# W103C.net
KiCad netlist of a schematic drawn in EAGLE
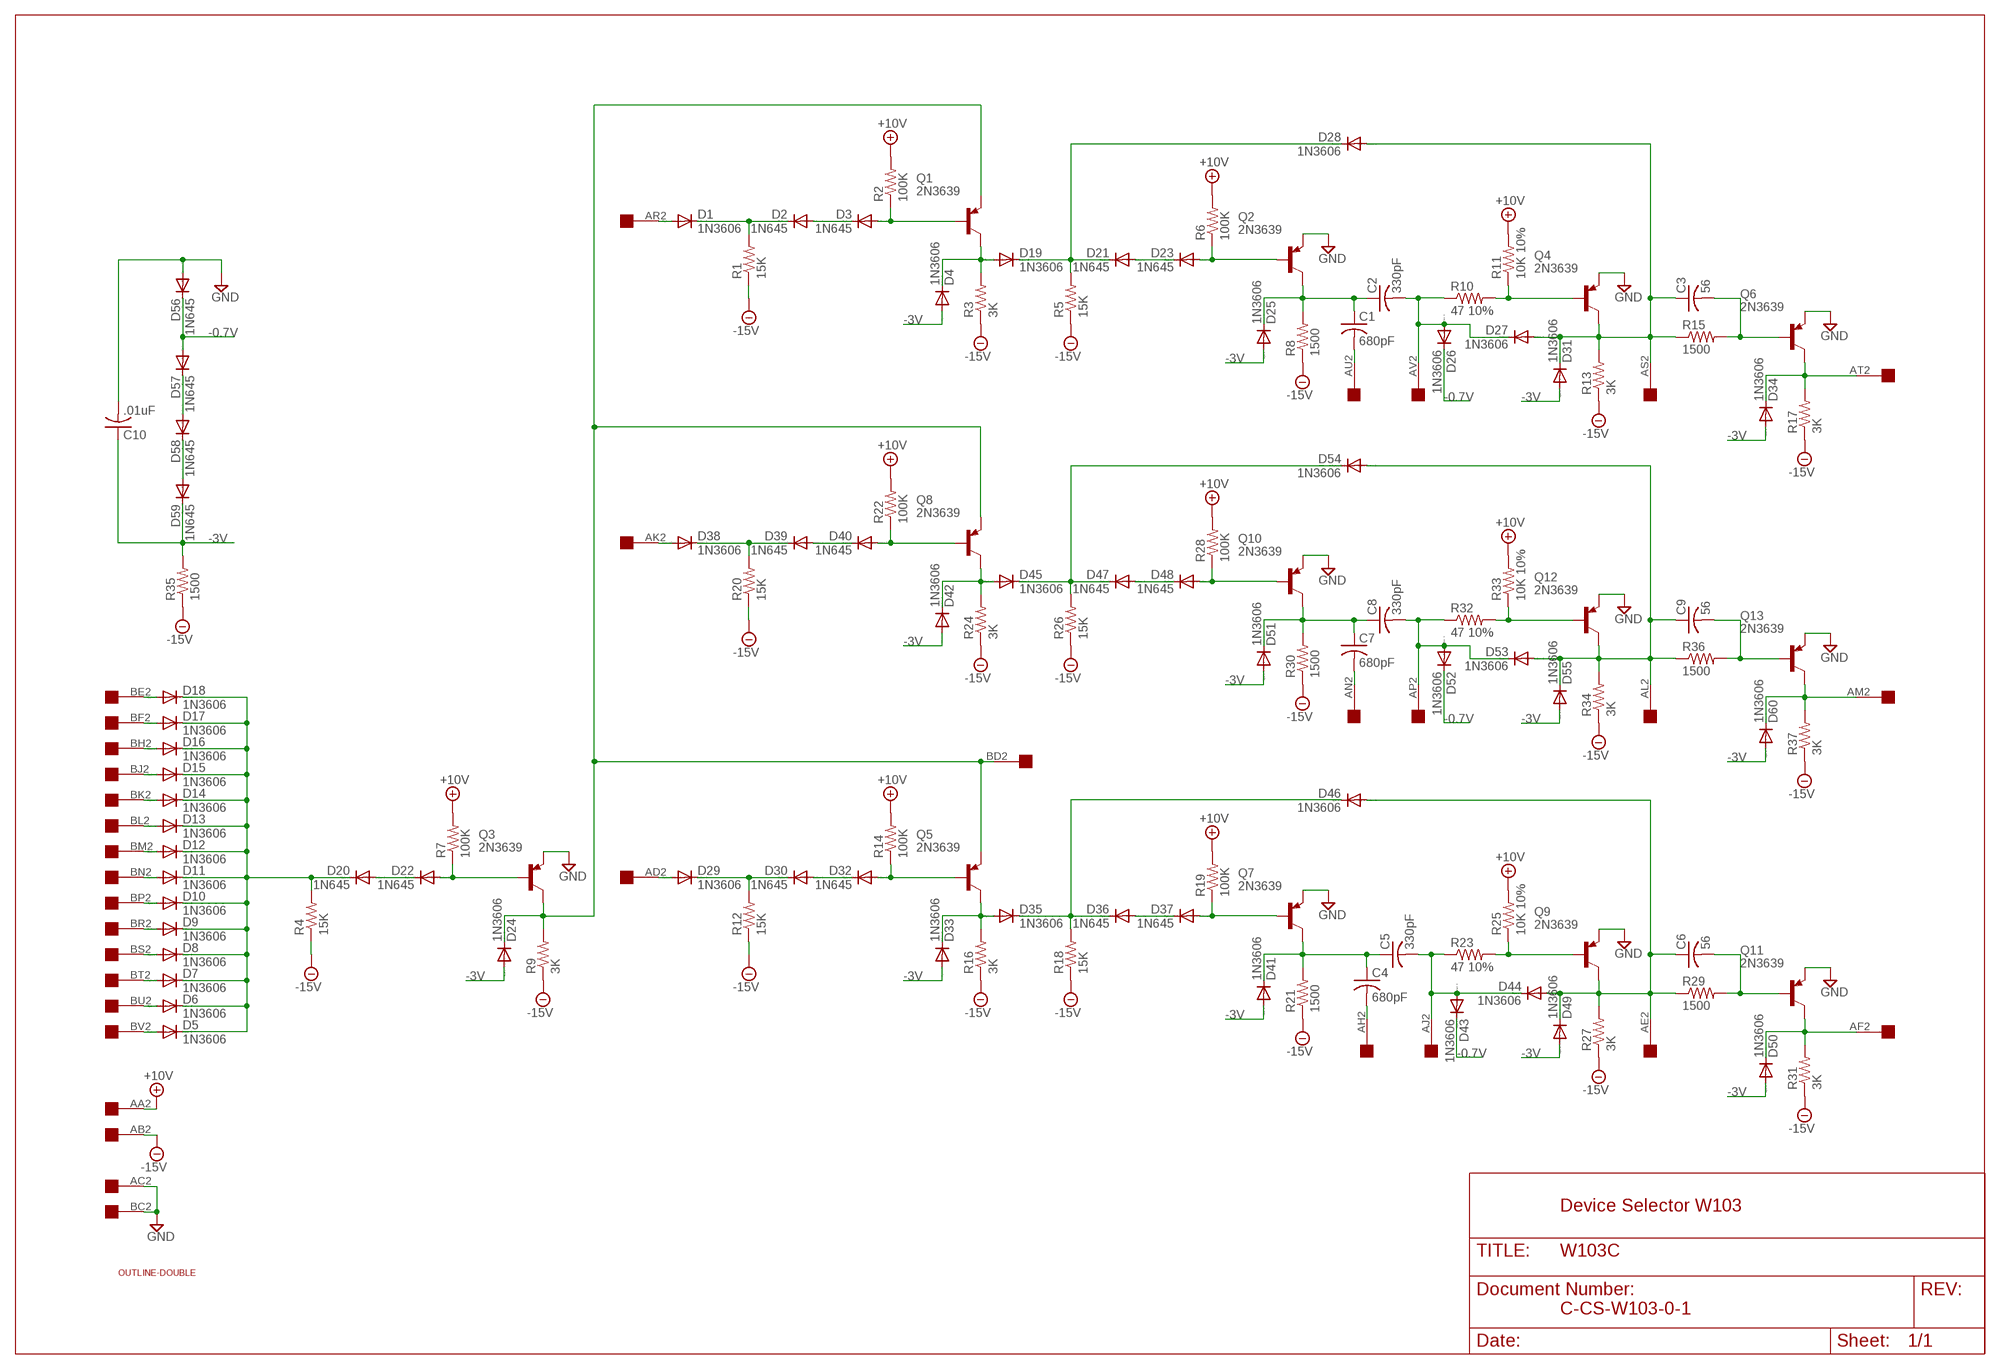
[diagram p0: schematic, sheet 1]

(export (version "E")
  (design (tool "Eeschema 10.0.6"))
  (components
    (comp (ref "C1")
      (value "680pF")
      (footprint "eagle-import:C075-032X103")
      (libsource (lib "eagle-import") (part "C-US075-032X103"))
    )
    (comp (ref "C2")
      (value "330pF")
      (footprint "eagle-import:C075-032X103")
      (libsource (lib "eagle-import") (part "C-US075-032X103"))
    )
    (comp (ref "C3")
      (value "56")
      (footprint "eagle-import:C075-032X103")
      (libsource (lib "eagle-import") (part "C-US075-032X103"))
    )
    (comp (ref "C4")
      (value "680pF")
      (footprint "eagle-import:C075-032X103")
      (libsource (lib "eagle-import") (part "C-US075-032X103"))
    )
    (comp (ref "C5")
      (value "330pF")
      (footprint "eagle-import:C075-032X103")
      (libsource (lib "eagle-import") (part "C-US075-032X103"))
    )
    (comp (ref "C6")
      (value "56")
      (footprint "eagle-import:C075-032X103")
      (libsource (lib "eagle-import") (part "C-US075-032X103"))
    )
    (comp (ref "C7")
      (value "680pF")
      (footprint "eagle-import:C075-032X103")
      (libsource (lib "eagle-import") (part "C-US075-032X103"))
    )
    (comp (ref "C8")
      (value "330pF")
      (footprint "eagle-import:C075-032X103")
      (libsource (lib "eagle-import") (part "C-US075-032X103"))
    )
    (comp (ref "C9")
      (value "56")
      (footprint "eagle-import:C075-032X103")
      (libsource (lib "eagle-import") (part "C-US075-032X103"))
    )
    (comp (ref "C10")
      (value ".01uF")
      (footprint "eagle-import:C075-032X103")
      (libsource (lib "eagle-import") (part "C-US075-032X103"))
    )
    (comp (ref "D1")
      (value "1N3606")
      (footprint "eagle-import:DO35-10")
      (libsource (lib "eagle-import") (part "1N4148DO35-10"))
    )
    (comp (ref "D2")
      (value "1N645")
      (footprint "eagle-import:DO35-10")
      (libsource (lib "eagle-import") (part "1N4148DO35-10"))
    )
    (comp (ref "D3")
      (value "1N645")
      (footprint "eagle-import:DO35-10")
      (libsource (lib "eagle-import") (part "1N4148DO35-10"))
    )
    (comp (ref "D4")
      (value "1N3606")
      (footprint "eagle-import:DO35-10")
      (libsource (lib "eagle-import") (part "1N4148DO35-10"))
    )
    (comp (ref "D5")
      (value "1N3606")
      (footprint "eagle-import:DO35-10")
      (libsource (lib "eagle-import") (part "1N4148DO35-10"))
    )
    (comp (ref "D6")
      (value "1N3606")
      (footprint "eagle-import:DO35-10")
      (libsource (lib "eagle-import") (part "1N4148DO35-10"))
    )
    (comp (ref "D7")
      (value "1N3606")
      (footprint "eagle-import:DO35-10")
      (libsource (lib "eagle-import") (part "1N4148DO35-10"))
    )
    (comp (ref "D8")
      (value "1N3606")
      (footprint "eagle-import:DO35-10")
      (libsource (lib "eagle-import") (part "1N4148DO35-10"))
    )
    (comp (ref "D9")
      (value "1N3606")
      (footprint "eagle-import:DO35-10")
      (libsource (lib "eagle-import") (part "1N4148DO35-10"))
    )
    (comp (ref "D10")
      (value "1N3606")
      (footprint "eagle-import:DO35-10")
      (libsource (lib "eagle-import") (part "1N4148DO35-10"))
    )
    (comp (ref "D11")
      (value "1N3606")
      (footprint "eagle-import:DO35-10")
      (libsource (lib "eagle-import") (part "1N4148DO35-10"))
    )
    (comp (ref "D12")
      (value "1N3606")
      (footprint "eagle-import:DO35-10")
      (libsource (lib "eagle-import") (part "1N4148DO35-10"))
    )
    (comp (ref "D13")
      (value "1N3606")
      (footprint "eagle-import:DO35-10")
      (libsource (lib "eagle-import") (part "1N4148DO35-10"))
    )
    (comp (ref "D14")
      (value "1N3606")
      (footprint "eagle-import:DO35-10")
      (libsource (lib "eagle-import") (part "1N4148DO35-10"))
    )
    (comp (ref "D15")
      (value "1N3606")
      (footprint "eagle-import:DO35-10")
      (libsource (lib "eagle-import") (part "1N4148DO35-10"))
    )
    (comp (ref "D16")
      (value "1N3606")
      (footprint "eagle-import:DO35-10")
      (libsource (lib "eagle-import") (part "1N4148DO35-10"))
    )
    (comp (ref "D17")
      (value "1N3606")
      (footprint "eagle-import:DO35-10")
      (libsource (lib "eagle-import") (part "1N4148DO35-10"))
    )
    (comp (ref "D18")
      (value "1N3606")
      (footprint "eagle-import:DO35-10")
      (libsource (lib "eagle-import") (part "1N4148DO35-10"))
    )
    (comp (ref "D19")
      (value "1N3606")
      (footprint "eagle-import:DO35-10")
      (libsource (lib "eagle-import") (part "1N4148DO35-10"))
    )
    (comp (ref "D20")
      (value "1N645")
      (footprint "eagle-import:DO35-10")
      (libsource (lib "eagle-import") (part "1N4148DO35-10"))
    )
    (comp (ref "D21")
      (value "1N645")
      (footprint "eagle-import:DO35-10")
      (libsource (lib "eagle-import") (part "1N4148DO35-10"))
    )
    (comp (ref "D22")
      (value "1N645")
      (footprint "eagle-import:DO35-10")
      (libsource (lib "eagle-import") (part "1N4148DO35-10"))
    )
    (comp (ref "D23")
      (value "1N645")
      (footprint "eagle-import:DO35-10")
      (libsource (lib "eagle-import") (part "1N4148DO35-10"))
    )
    (comp (ref "D24")
      (value "1N3606")
      (footprint "eagle-import:DO35-10")
      (libsource (lib "eagle-import") (part "1N4148DO35-10"))
    )
    (comp (ref "D25")
      (value "1N3606")
      (footprint "eagle-import:DO35-10")
      (libsource (lib "eagle-import") (part "1N4148DO35-10"))
    )
    (comp (ref "D26")
      (value "1N3606")
      (footprint "eagle-import:DO35-10")
      (libsource (lib "eagle-import") (part "1N4148DO35-10"))
    )
    (comp (ref "D27")
      (value "1N3606")
      (footprint "eagle-import:DO35-10")
      (libsource (lib "eagle-import") (part "1N4148DO35-10"))
    )
    (comp (ref "D28")
      (value "1N3606")
      (footprint "eagle-import:DO35-10")
      (libsource (lib "eagle-import") (part "1N4148DO35-10"))
    )
    (comp (ref "D29")
      (value "1N3606")
      (footprint "eagle-import:DO35-10")
      (libsource (lib "eagle-import") (part "1N4148DO35-10"))
    )
    (comp (ref "D30")
      (value "1N645")
      (footprint "eagle-import:DO35-10")
      (libsource (lib "eagle-import") (part "1N4148DO35-10"))
    )
    (comp (ref "D31")
      (value "1N3606")
      (footprint "eagle-import:DO35-10")
      (libsource (lib "eagle-import") (part "1N4148DO35-10"))
    )
    (comp (ref "D32")
      (value "1N645")
      (footprint "eagle-import:DO35-10")
      (libsource (lib "eagle-import") (part "1N4148DO35-10"))
    )
    (comp (ref "D33")
      (value "1N3606")
      (footprint "eagle-import:DO35-10")
      (libsource (lib "eagle-import") (part "1N4148DO35-10"))
    )
    (comp (ref "D34")
      (value "1N3606")
      (footprint "eagle-import:DO35-10")
      (libsource (lib "eagle-import") (part "1N4148DO35-10"))
    )
    (comp (ref "D35")
      (value "1N3606")
      (footprint "eagle-import:DO35-10")
      (libsource (lib "eagle-import") (part "1N4148DO35-10"))
    )
    (comp (ref "D36")
      (value "1N645")
      (footprint "eagle-import:DO35-10")
      (libsource (lib "eagle-import") (part "1N4148DO35-10"))
    )
    (comp (ref "D37")
      (value "1N645")
      (footprint "eagle-import:DO35-10")
      (libsource (lib "eagle-import") (part "1N4148DO35-10"))
    )
    (comp (ref "D38")
      (value "1N3606")
      (footprint "eagle-import:DO35-10")
      (libsource (lib "eagle-import") (part "1N4148DO35-10"))
    )
    (comp (ref "D39")
      (value "1N645")
      (footprint "eagle-import:DO35-10")
      (libsource (lib "eagle-import") (part "1N4148DO35-10"))
    )
    (comp (ref "D40")
      (value "1N645")
      (footprint "eagle-import:DO35-10")
      (libsource (lib "eagle-import") (part "1N4148DO35-10"))
    )
    (comp (ref "D41")
      (value "1N3606")
      (footprint "eagle-import:DO35-10")
      (libsource (lib "eagle-import") (part "1N4148DO35-10"))
    )
    (comp (ref "D42")
      (value "1N3606")
      (footprint "eagle-import:DO35-10")
      (libsource (lib "eagle-import") (part "1N4148DO35-10"))
    )
    (comp (ref "D43")
      (value "1N3606")
      (footprint "eagle-import:DO35-10")
      (libsource (lib "eagle-import") (part "1N4148DO35-10"))
    )
    (comp (ref "D44")
      (value "1N3606")
      (footprint "eagle-import:DO35-10")
      (libsource (lib "eagle-import") (part "1N4148DO35-10"))
    )
    (comp (ref "D45")
      (value "1N3606")
      (footprint "eagle-import:DO35-10")
      (libsource (lib "eagle-import") (part "1N4148DO35-10"))
    )
    (comp (ref "D46")
      (value "1N3606")
      (footprint "eagle-import:DO35-10")
      (libsource (lib "eagle-import") (part "1N4148DO35-10"))
    )
    (comp (ref "D47")
      (value "1N645")
      (footprint "eagle-import:DO35-10")
      (libsource (lib "eagle-import") (part "1N4148DO35-10"))
    )
    (comp (ref "D48")
      (value "1N645")
      (footprint "eagle-import:DO35-10")
      (libsource (lib "eagle-import") (part "1N4148DO35-10"))
    )
    (comp (ref "D49")
      (value "1N3606")
      (footprint "eagle-import:DO35-10")
      (libsource (lib "eagle-import") (part "1N4148DO35-10"))
    )
    (comp (ref "D50")
      (value "1N3606")
      (footprint "eagle-import:DO35-10")
      (libsource (lib "eagle-import") (part "1N4148DO35-10"))
    )
    (comp (ref "D51")
      (value "1N3606")
      (footprint "eagle-import:DO35-10")
      (libsource (lib "eagle-import") (part "1N4148DO35-10"))
    )
    (comp (ref "D52")
      (value "1N3606")
      (footprint "eagle-import:DO35-10")
      (libsource (lib "eagle-import") (part "1N4148DO35-10"))
    )
    (comp (ref "D53")
      (value "1N3606")
      (footprint "eagle-import:DO35-10")
      (libsource (lib "eagle-import") (part "1N4148DO35-10"))
    )
    (comp (ref "D54")
      (value "1N3606")
      (footprint "eagle-import:DO35-10")
      (libsource (lib "eagle-import") (part "1N4148DO35-10"))
    )
    (comp (ref "D55")
      (value "1N3606")
      (footprint "eagle-import:DO35-10")
      (libsource (lib "eagle-import") (part "1N4148DO35-10"))
    )
    (comp (ref "D56")
      (value "1N645")
      (footprint "eagle-import:DO35-10")
      (libsource (lib "eagle-import") (part "1N4148DO35-10"))
    )
    (comp (ref "D57")
      (value "1N645")
      (footprint "eagle-import:DO35-10")
      (libsource (lib "eagle-import") (part "1N4148DO35-10"))
    )
    (comp (ref "D58")
      (value "1N645")
      (footprint "eagle-import:DO35-10")
      (libsource (lib "eagle-import") (part "1N4148DO35-10"))
    )
    (comp (ref "D59")
      (value "1N645")
      (footprint "eagle-import:DO35-10")
      (libsource (lib "eagle-import") (part "1N4148DO35-10"))
    )
    (comp (ref "D60")
      (value "1N3606")
      (footprint "eagle-import:DO35-10")
      (libsource (lib "eagle-import") (part "1N4148DO35-10"))
    )
    (comp (ref "Q1")
      (value "2N3639")
      (footprint "eagle-import:TO39")
      (libsource (lib "eagle-import") (part "2N2904"))
    )
    (comp (ref "Q2")
      (value "2N3639")
      (footprint "eagle-import:TO39")
      (libsource (lib "eagle-import") (part "2N2904"))
    )
    (comp (ref "Q3")
      (value "2N3639")
      (footprint "eagle-import:TO39")
      (libsource (lib "eagle-import") (part "2N2904"))
    )
    (comp (ref "Q4")
      (value "2N3639")
      (footprint "eagle-import:TO39")
      (libsource (lib "eagle-import") (part "2N2904"))
    )
    (comp (ref "Q5")
      (value "2N3639")
      (footprint "eagle-import:TO39")
      (libsource (lib "eagle-import") (part "2N2904"))
    )
    (comp (ref "Q6")
      (value "2N3639")
      (footprint "eagle-import:TO39")
      (libsource (lib "eagle-import") (part "2N2904"))
    )
    (comp (ref "Q7")
      (value "2N3639")
      (footprint "eagle-import:TO39")
      (libsource (lib "eagle-import") (part "2N2904"))
    )
    (comp (ref "Q8")
      (value "2N3639")
      (footprint "eagle-import:TO39")
      (libsource (lib "eagle-import") (part "2N2904"))
    )
    (comp (ref "Q9")
      (value "2N3639")
      (footprint "eagle-import:TO39")
      (libsource (lib "eagle-import") (part "2N2904"))
    )
    (comp (ref "Q10")
      (value "2N3639")
      (footprint "eagle-import:TO39")
      (libsource (lib "eagle-import") (part "2N2904"))
    )
    (comp (ref "Q11")
      (value "2N3639")
      (footprint "eagle-import:TO39")
      (libsource (lib "eagle-import") (part "2N2904"))
    )
    (comp (ref "Q12")
      (value "2N3639")
      (footprint "eagle-import:TO39")
      (libsource (lib "eagle-import") (part "2N2904"))
    )
    (comp (ref "Q13")
      (value "2N3639")
      (footprint "eagle-import:TO39")
      (libsource (lib "eagle-import") (part "2N2904"))
    )
    (comp (ref "R1")
      (value "15K")
      (footprint "eagle-import:0207_10")
      (libsource (lib "eagle-import") (part "R-US_0207/10"))
    )
    (comp (ref "R2")
      (value "100K")
      (footprint "eagle-import:0207_10")
      (libsource (lib "eagle-import") (part "R-US_0207/10"))
    )
    (comp (ref "R3")
      (value "3K")
      (footprint "eagle-import:0207_10")
      (libsource (lib "eagle-import") (part "R-US_0207/10"))
    )
    (comp (ref "R4")
      (value "15K")
      (footprint "eagle-import:0207_10")
      (libsource (lib "eagle-import") (part "R-US_0207/10"))
    )
    (comp (ref "R5")
      (value "15K")
      (footprint "eagle-import:0207_10")
      (libsource (lib "eagle-import") (part "R-US_0207/10"))
    )
    (comp (ref "R6")
      (value "100K")
      (footprint "eagle-import:0207_10")
      (libsource (lib "eagle-import") (part "R-US_0207/10"))
    )
    (comp (ref "R7")
      (value "100K")
      (footprint "eagle-import:0207_10")
      (libsource (lib "eagle-import") (part "R-US_0207/10"))
    )
    (comp (ref "R8")
      (value "1500")
      (footprint "eagle-import:0207_10")
      (libsource (lib "eagle-import") (part "R-US_0207/10"))
    )
    (comp (ref "R9")
      (value "3K")
      (footprint "eagle-import:0207_10")
      (libsource (lib "eagle-import") (part "R-US_0207/10"))
    )
    (comp (ref "R10")
      (value "47 10%")
      (footprint "eagle-import:0207_10")
      (libsource (lib "eagle-import") (part "R-US_0207/10"))
    )
    (comp (ref "R11")
      (value "10K 10%")
      (footprint "eagle-import:0207_10")
      (libsource (lib "eagle-import") (part "R-US_0207/10"))
    )
    (comp (ref "R12")
      (value "15K")
      (footprint "eagle-import:0207_10")
      (libsource (lib "eagle-import") (part "R-US_0207/10"))
    )
    (comp (ref "R13")
      (value "3K")
      (footprint "eagle-import:0207_10")
      (libsource (lib "eagle-import") (part "R-US_0207/10"))
    )
    (comp (ref "R14")
      (value "100K")
      (footprint "eagle-import:0207_10")
      (libsource (lib "eagle-import") (part "R-US_0207/10"))
    )
    (comp (ref "R15")
      (value "1500")
      (footprint "eagle-import:0207_10")
      (libsource (lib "eagle-import") (part "R-US_0207/10"))
    )
    (comp (ref "R16")
      (value "3K")
      (footprint "eagle-import:0207_10")
      (libsource (lib "eagle-import") (part "R-US_0207/10"))
    )
    (comp (ref "R17")
      (value "3K")
      (footprint "eagle-import:0207_10")
      (libsource (lib "eagle-import") (part "R-US_0207/10"))
    )
    (comp (ref "R18")
      (value "15K")
      (footprint "eagle-import:0207_10")
      (libsource (lib "eagle-import") (part "R-US_0207/10"))
    )
    (comp (ref "R19")
      (value "100K")
      (footprint "eagle-import:0207_10")
      (libsource (lib "eagle-import") (part "R-US_0207/10"))
    )
    (comp (ref "R20")
      (value "15K")
      (footprint "eagle-import:0207_10")
      (libsource (lib "eagle-import") (part "R-US_0207/10"))
    )
    (comp (ref "R21")
      (value "1500")
      (footprint "eagle-import:0207_10")
      (libsource (lib "eagle-import") (part "R-US_0207/10"))
    )
    (comp (ref "R22")
      (value "100K")
      (footprint "eagle-import:0207_10")
      (libsource (lib "eagle-import") (part "R-US_0207/10"))
    )
    (comp (ref "R23")
      (value "47 10%")
      (footprint "eagle-import:0207_10")
      (libsource (lib "eagle-import") (part "R-US_0207/10"))
    )
    (comp (ref "R24")
      (value "3K")
      (footprint "eagle-import:0207_10")
      (libsource (lib "eagle-import") (part "R-US_0207/10"))
    )
    (comp (ref "R25")
      (value "10K 10%")
      (footprint "eagle-import:0207_10")
      (libsource (lib "eagle-import") (part "R-US_0207/10"))
    )
    (comp (ref "R26")
      (value "15K")
      (footprint "eagle-import:0207_10")
      (libsource (lib "eagle-import") (part "R-US_0207/10"))
    )
    (comp (ref "R27")
      (value "3K")
      (footprint "eagle-import:0207_10")
      (libsource (lib "eagle-import") (part "R-US_0207/10"))
    )
    (comp (ref "R28")
      (value "100K")
      (footprint "eagle-import:0207_10")
      (libsource (lib "eagle-import") (part "R-US_0207/10"))
    )
    (comp (ref "R29")
      (value "1500")
      (footprint "eagle-import:0207_10")
      (libsource (lib "eagle-import") (part "R-US_0207/10"))
    )
    (comp (ref "R30")
      (value "1500")
      (footprint "eagle-import:0207_10")
      (libsource (lib "eagle-import") (part "R-US_0207/10"))
    )
    (comp (ref "R31")
      (value "3K")
      (footprint "eagle-import:0207_10")
      (libsource (lib "eagle-import") (part "R-US_0207/10"))
    )
    (comp (ref "R32")
      (value "47 10%")
      (footprint "eagle-import:0207_10")
      (libsource (lib "eagle-import") (part "R-US_0207/10"))
    )
    (comp (ref "R33")
      (value "10K 10%")
      (footprint "eagle-import:0207_10")
      (libsource (lib "eagle-import") (part "R-US_0207/10"))
    )
    (comp (ref "R34")
      (value "3K")
      (footprint "eagle-import:0207_10")
      (libsource (lib "eagle-import") (part "R-US_0207/10"))
    )
    (comp (ref "R35")
      (value "1500")
      (footprint "eagle-import:0207_10")
      (libsource (lib "eagle-import") (part "R-US_0207/10"))
    )
    (comp (ref "R36")
      (value "1500")
      (footprint "eagle-import:0207_10")
      (libsource (lib "eagle-import") (part "R-US_0207/10"))
    )
    (comp (ref "R37")
      (value "3K")
      (footprint "eagle-import:0207_10")
      (libsource (lib "eagle-import") (part "R-US_0207/10"))
    )
    (comp (ref "U$1")
      (value "OUTLINE-DOUBLE")
      (footprint "eagle-import:DOUBLE")
      (libsource (lib "eagle-import") (part "OUTLINE-DOUBLE"))
    )
    (comp (ref "U$2")
      (value "DOUBLE")
      (footprint "eagle-import:EDGE-CON4")
      (libsource (lib "eagle-import") (part "DOUBLE"))
    )
  )
  (nets
    (net (code "1") (name "+10V") (class "Default")
      (node (ref "R11") (pin "2") (pinfunction "2_2") (pintype "passive"))
      (node (ref "R14") (pin "2") (pinfunction "2_2") (pintype "passive"))
      (node (ref "R19") (pin "2") (pinfunction "2_2") (pintype "passive"))
      (node (ref "R2") (pin "2") (pinfunction "2_2") (pintype "passive"))
      (node (ref "R22") (pin "2") (pinfunction "2_2") (pintype "passive"))
      (node (ref "R25") (pin "2") (pinfunction "2_2") (pintype "passive"))
      (node (ref "R28") (pin "2") (pinfunction "2_2") (pintype "passive"))
      (node (ref "R33") (pin "2") (pinfunction "2_2") (pintype "passive"))
      (node (ref "R6") (pin "2") (pinfunction "2_2") (pintype "passive"))
      (node (ref "R7") (pin "2") (pinfunction "2_2") (pintype "passive"))
      (node (ref "U$2") (pin "AA2") (pinfunction "1_AA2") (pintype "bidirectional"))
    )
    (net (code "2") (name "-15V") (class "Default")
      (node (ref "R1") (pin "1") (pinfunction "1_1") (pintype "passive"))
      (node (ref "R12") (pin "1") (pinfunction "1_1") (pintype "passive"))
      (node (ref "R13") (pin "1") (pinfunction "1_1") (pintype "passive"))
      (node (ref "R16") (pin "1") (pinfunction "1_1") (pintype "passive"))
      (node (ref "R17") (pin "1") (pinfunction "1_1") (pintype "passive"))
      (node (ref "R18") (pin "1") (pinfunction "1_1") (pintype "passive"))
      (node (ref "R20") (pin "1") (pinfunction "1_1") (pintype "passive"))
      (node (ref "R21") (pin "1") (pinfunction "1_1") (pintype "passive"))
      (node (ref "R24") (pin "1") (pinfunction "1_1") (pintype "passive"))
      (node (ref "R26") (pin "1") (pinfunction "1_1") (pintype "passive"))
      (node (ref "R27") (pin "1") (pinfunction "1_1") (pintype "passive"))
      (node (ref "R3") (pin "1") (pinfunction "1_1") (pintype "passive"))
      (node (ref "R30") (pin "1") (pinfunction "1_1") (pintype "passive"))
      (node (ref "R31") (pin "1") (pinfunction "1_1") (pintype "passive"))
      (node (ref "R34") (pin "1") (pinfunction "1_1") (pintype "passive"))
      (node (ref "R35") (pin "1") (pinfunction "1_1") (pintype "passive"))
      (node (ref "R37") (pin "1") (pinfunction "1_1") (pintype "passive"))
      (node (ref "R4") (pin "1") (pinfunction "1_1") (pintype "passive"))
      (node (ref "R5") (pin "1") (pinfunction "1_1") (pintype "passive"))
      (node (ref "R8") (pin "1") (pinfunction "1_1") (pintype "passive"))
      (node (ref "R9") (pin "1") (pinfunction "1_1") (pintype "passive"))
      (node (ref "U$2") (pin "AB2") (pinfunction "1_AB2") (pintype "bidirectional"))
    )
    (net (code "3") (name "/-0.7V") (class "Default")
      (node (ref "D26") (pin "C") (pinfunction "C_C") (pintype "passive"))
      (node (ref "D43") (pin "C") (pinfunction "C_C") (pintype "passive"))
      (node (ref "D52") (pin "C") (pinfunction "C_C") (pintype "passive"))
      (node (ref "D56") (pin "C") (pinfunction "C_C") (pintype "passive"))
      (node (ref "D57") (pin "A") (pinfunction "A_A") (pintype "passive"))
    )
    (net (code "4") (name "/-3V") (class "Default")
      (node (ref "C10") (pin "1") (pinfunction "1_1") (pintype "passive"))
      (node (ref "D24") (pin "A") (pinfunction "A_A") (pintype "passive"))
      (node (ref "D25") (pin "A") (pinfunction "A_A") (pintype "passive"))
      (node (ref "D31") (pin "A") (pinfunction "A_A") (pintype "passive"))
      (node (ref "D33") (pin "A") (pinfunction "A_A") (pintype "passive"))
      (node (ref "D34") (pin "A") (pinfunction "A_A") (pintype "passive"))
      (node (ref "D4") (pin "A") (pinfunction "A_A") (pintype "passive"))
      (node (ref "D41") (pin "A") (pinfunction "A_A") (pintype "passive"))
      (node (ref "D42") (pin "A") (pinfunction "A_A") (pintype "passive"))
      (node (ref "D49") (pin "A") (pinfunction "A_A") (pintype "passive"))
      (node (ref "D50") (pin "A") (pinfunction "A_A") (pintype "passive"))
      (node (ref "D51") (pin "A") (pinfunction "A_A") (pintype "passive"))
      (node (ref "D55") (pin "A") (pinfunction "A_A") (pintype "passive"))
      (node (ref "D59") (pin "C") (pinfunction "C_C") (pintype "passive"))
      (node (ref "D60") (pin "A") (pinfunction "A_A") (pintype "passive"))
      (node (ref "R35") (pin "2") (pinfunction "2_2") (pintype "passive"))
    )
    (net (code "5") (name "GND") (class "Default")
      (node (ref "C10") (pin "2") (pinfunction "2_2") (pintype "passive"))
      (node (ref "D56") (pin "A") (pinfunction "A_A") (pintype "passive"))
      (node (ref "Q10") (pin "1") (pinfunction "E_1") (pintype "passive"))
      (node (ref "Q11") (pin "1") (pinfunction "E_1") (pintype "passive"))
      (node (ref "Q12") (pin "1") (pinfunction "E_1") (pintype "passive"))
      (node (ref "Q13") (pin "1") (pinfunction "E_1") (pintype "passive"))
      (node (ref "Q2") (pin "1") (pinfunction "E_1") (pintype "passive"))
      (node (ref "Q3") (pin "1") (pinfunction "E_1") (pintype "passive"))
      (node (ref "Q4") (pin "1") (pinfunction "E_1") (pintype "passive"))
      (node (ref "Q6") (pin "1") (pinfunction "E_1") (pintype "passive"))
      (node (ref "Q7") (pin "1") (pinfunction "E_1") (pintype "passive"))
      (node (ref "Q9") (pin "1") (pinfunction "E_1") (pintype "passive"))
      (node (ref "U$2") (pin "AC2") (pinfunction "1_AC2") (pintype "bidirectional"))
      (node (ref "U$2") (pin "BC2") (pinfunction "1_BC2") (pintype "bidirectional"))
    )
    (net (code "6") (name "Net-(D1-PadC)") (class "Default")
      (node (ref "D1") (pin "C") (pinfunction "C_C") (pintype "passive"))
      (node (ref "D2") (pin "C") (pinfunction "C_C") (pintype "passive"))
      (node (ref "R1") (pin "2") (pinfunction "2_2") (pintype "passive"))
    )
    (net (code "7") (name "Net-(D2-PadA)") (class "Default")
      (node (ref "D2") (pin "A") (pinfunction "A_A") (pintype "passive"))
      (node (ref "D3") (pin "C") (pinfunction "C_C") (pintype "passive"))
    )
    (net (code "8") (name "Net-(D10-PadC)") (class "Default")
      (node (ref "D10") (pin "C") (pinfunction "C_C") (pintype "passive"))
      (node (ref "D11") (pin "C") (pinfunction "C_C") (pintype "passive"))
      (node (ref "D12") (pin "C") (pinfunction "C_C") (pintype "passive"))
      (node (ref "D13") (pin "C") (pinfunction "C_C") (pintype "passive"))
      (node (ref "D14") (pin "C") (pinfunction "C_C") (pintype "passive"))
      (node (ref "D15") (pin "C") (pinfunction "C_C") (pintype "passive"))
      (node (ref "D16") (pin "C") (pinfunction "C_C") (pintype "passive"))
      (node (ref "D17") (pin "C") (pinfunction "C_C") (pintype "passive"))
      (node (ref "D18") (pin "C") (pinfunction "C_C") (pintype "passive"))
      (node (ref "D20") (pin "C") (pinfunction "C_C") (pintype "passive"))
      (node (ref "D5") (pin "C") (pinfunction "C_C") (pintype "passive"))
      (node (ref "D6") (pin "C") (pinfunction "C_C") (pintype "passive"))
      (node (ref "D7") (pin "C") (pinfunction "C_C") (pintype "passive"))
      (node (ref "D8") (pin "C") (pinfunction "C_C") (pintype "passive"))
      (node (ref "D9") (pin "C") (pinfunction "C_C") (pintype "passive"))
      (node (ref "R4") (pin "2") (pinfunction "2_2") (pintype "passive"))
    )
    (net (code "9") (name "Net-(D19-PadC)") (class "Default")
      (node (ref "D19") (pin "C") (pinfunction "C_C") (pintype "passive"))
      (node (ref "D21") (pin "C") (pinfunction "C_C") (pintype "passive"))
      (node (ref "D28") (pin "C") (pinfunction "C_C") (pintype "passive"))
      (node (ref "R5") (pin "2") (pinfunction "2_2") (pintype "passive"))
    )
    (net (code "10") (name "Net-(D20-PadA)") (class "Default")
      (node (ref "D20") (pin "A") (pinfunction "A_A") (pintype "passive"))
      (node (ref "D22") (pin "C") (pinfunction "C_C") (pintype "passive"))
    )
    (net (code "11") (name "Net-(D21-PadA)") (class "Default")
      (node (ref "D21") (pin "A") (pinfunction "A_A") (pintype "passive"))
      (node (ref "D23") (pin "C") (pinfunction "C_C") (pintype "passive"))
    )
    (net (code "12") (name "Net-(D29-PadC)") (class "Default")
      (node (ref "D29") (pin "C") (pinfunction "C_C") (pintype "passive"))
      (node (ref "D30") (pin "C") (pinfunction "C_C") (pintype "passive"))
      (node (ref "R12") (pin "2") (pinfunction "2_2") (pintype "passive"))
    )
    (net (code "13") (name "Net-(D30-PadA)") (class "Default")
      (node (ref "D30") (pin "A") (pinfunction "A_A") (pintype "passive"))
      (node (ref "D32") (pin "C") (pinfunction "C_C") (pintype "passive"))
    )
    (net (code "14") (name "Net-(D35-PadC)") (class "Default")
      (node (ref "D35") (pin "C") (pinfunction "C_C") (pintype "passive"))
      (node (ref "D36") (pin "C") (pinfunction "C_C") (pintype "passive"))
      (node (ref "D46") (pin "C") (pinfunction "C_C") (pintype "passive"))
      (node (ref "R18") (pin "2") (pinfunction "2_2") (pintype "passive"))
    )
    (net (code "15") (name "Net-(D36-PadA)") (class "Default")
      (node (ref "D36") (pin "A") (pinfunction "A_A") (pintype "passive"))
      (node (ref "D37") (pin "C") (pinfunction "C_C") (pintype "passive"))
    )
    (net (code "16") (name "Net-(D38-PadC)") (class "Default")
      (node (ref "D38") (pin "C") (pinfunction "C_C") (pintype "passive"))
      (node (ref "D39") (pin "C") (pinfunction "C_C") (pintype "passive"))
      (node (ref "R20") (pin "2") (pinfunction "2_2") (pintype "passive"))
    )
    (net (code "17") (name "Net-(D39-PadA)") (class "Default")
      (node (ref "D39") (pin "A") (pinfunction "A_A") (pintype "passive"))
      (node (ref "D40") (pin "C") (pinfunction "C_C") (pintype "passive"))
    )
    (net (code "18") (name "Net-(D45-PadC)") (class "Default")
      (node (ref "D45") (pin "C") (pinfunction "C_C") (pintype "passive"))
      (node (ref "D47") (pin "C") (pinfunction "C_C") (pintype "passive"))
      (node (ref "D54") (pin "C") (pinfunction "C_C") (pintype "passive"))
      (node (ref "R26") (pin "2") (pinfunction "2_2") (pintype "passive"))
    )
    (net (code "19") (name "Net-(D47-PadA)") (class "Default")
      (node (ref "D47") (pin "A") (pinfunction "A_A") (pintype "passive"))
      (node (ref "D48") (pin "C") (pinfunction "C_C") (pintype "passive"))
    )
    (net (code "20") (name "Net-(D57-PadC)") (class "Default")
      (node (ref "D57") (pin "C") (pinfunction "C_C") (pintype "passive"))
      (node (ref "D58") (pin "A") (pinfunction "A_A") (pintype "passive"))
    )
    (net (code "21") (name "Net-(D58-PadC)") (class "Default")
      (node (ref "D58") (pin "C") (pinfunction "C_C") (pintype "passive"))
      (node (ref "D59") (pin "A") (pinfunction "A_A") (pintype "passive"))
    )
    (net (code "22") (name "Net-(Q1-B)") (class "Default")
      (node (ref "D3") (pin "A") (pinfunction "A_A") (pintype "passive"))
      (node (ref "Q1") (pin "2") (pinfunction "B_2") (pintype "passive"))
      (node (ref "R2") (pin "1") (pinfunction "1_1") (pintype "passive"))
    )
    (net (code "23") (name "Net-(Q1-C)") (class "Default")
      (node (ref "D19") (pin "A") (pinfunction "A_A") (pintype "passive"))
      (node (ref "D4") (pin "C") (pinfunction "C_C") (pintype "passive"))
      (node (ref "Q1") (pin "3") (pinfunction "C_3") (pintype "passive"))
      (node (ref "R3") (pin "2") (pinfunction "2_2") (pintype "passive"))
    )
    (net (code "24") (name "Net-(Q1-E)") (class "Default")
      (node (ref "D24") (pin "C") (pinfunction "C_C") (pintype "passive"))
      (node (ref "Q1") (pin "1") (pinfunction "E_1") (pintype "passive"))
      (node (ref "Q3") (pin "3") (pinfunction "C_3") (pintype "passive"))
      (node (ref "Q5") (pin "1") (pinfunction "E_1") (pintype "passive"))
      (node (ref "Q8") (pin "1") (pinfunction "E_1") (pintype "passive"))
      (node (ref "R9") (pin "2") (pinfunction "2_2") (pintype "passive"))
      (node (ref "U$2") (pin "BD2") (pinfunction "1_BD2") (pintype "bidirectional"))
    )
    (net (code "25") (name "Net-(Q2-B)") (class "Default")
      (node (ref "D23") (pin "A") (pinfunction "A_A") (pintype "passive"))
      (node (ref "Q2") (pin "2") (pinfunction "B_2") (pintype "passive"))
      (node (ref "R6") (pin "1") (pinfunction "1_1") (pintype "passive"))
    )
    (net (code "26") (name "Net-(Q2-C)") (class "Default")
      (node (ref "C1") (pin "1") (pinfunction "1_1") (pintype "passive"))
      (node (ref "C2") (pin "1") (pinfunction "1_1") (pintype "passive"))
      (node (ref "D25") (pin "C") (pinfunction "C_C") (pintype "passive"))
      (node (ref "Q2") (pin "3") (pinfunction "C_3") (pintype "passive"))
      (node (ref "R8") (pin "2") (pinfunction "2_2") (pintype "passive"))
    )
    (net (code "27") (name "Net-(Q3-B)") (class "Default")
      (node (ref "D22") (pin "A") (pinfunction "A_A") (pintype "passive"))
      (node (ref "Q3") (pin "2") (pinfunction "B_2") (pintype "passive"))
      (node (ref "R7") (pin "1") (pinfunction "1_1") (pintype "passive"))
    )
    (net (code "28") (name "Net-(Q4-B)") (class "Default")
      (node (ref "Q4") (pin "2") (pinfunction "B_2") (pintype "passive"))
      (node (ref "R10") (pin "2") (pinfunction "2_2") (pintype "passive"))
      (node (ref "R11") (pin "1") (pinfunction "1_1") (pintype "passive"))
    )
    (net (code "29") (name "Net-(Q4-C)") (class "Default")
      (node (ref "C3") (pin "1") (pinfunction "1_1") (pintype "passive"))
      (node (ref "D27") (pin "A") (pinfunction "A_A") (pintype "passive"))
      (node (ref "D28") (pin "A") (pinfunction "A_A") (pintype "passive"))
      (node (ref "D31") (pin "C") (pinfunction "C_C") (pintype "passive"))
      (node (ref "Q4") (pin "3") (pinfunction "C_3") (pintype "passive"))
      (node (ref "R13") (pin "2") (pinfunction "2_2") (pintype "passive"))
      (node (ref "R15") (pin "1") (pinfunction "1_1") (pintype "passive"))
      (node (ref "U$2") (pin "AS2") (pinfunction "1_AS2") (pintype "bidirectional"))
    )
    (net (code "30") (name "Net-(Q5-B)") (class "Default")
      (node (ref "D32") (pin "A") (pinfunction "A_A") (pintype "passive"))
      (node (ref "Q5") (pin "2") (pinfunction "B_2") (pintype "passive"))
      (node (ref "R14") (pin "1") (pinfunction "1_1") (pintype "passive"))
    )
    (net (code "31") (name "Net-(Q5-C)") (class "Default")
      (node (ref "D33") (pin "C") (pinfunction "C_C") (pintype "passive"))
      (node (ref "D35") (pin "A") (pinfunction "A_A") (pintype "passive"))
      (node (ref "Q5") (pin "3") (pinfunction "C_3") (pintype "passive"))
      (node (ref "R16") (pin "2") (pinfunction "2_2") (pintype "passive"))
    )
    (net (code "32") (name "Net-(Q6-B)") (class "Default")
      (node (ref "C3") (pin "2") (pinfunction "2_2") (pintype "passive"))
      (node (ref "Q6") (pin "2") (pinfunction "B_2") (pintype "passive"))
      (node (ref "R15") (pin "2") (pinfunction "2_2") (pintype "passive"))
    )
    (net (code "33") (name "Net-(Q6-C)") (class "Default")
      (node (ref "D34") (pin "C") (pinfunction "C_C") (pintype "passive"))
      (node (ref "Q6") (pin "3") (pinfunction "C_3") (pintype "passive"))
      (node (ref "R17") (pin "2") (pinfunction "2_2") (pintype "passive"))
      (node (ref "U$2") (pin "AT2") (pinfunction "1_AT2") (pintype "bidirectional"))
    )
    (net (code "34") (name "Net-(Q7-B)") (class "Default")
      (node (ref "D37") (pin "A") (pinfunction "A_A") (pintype "passive"))
      (node (ref "Q7") (pin "2") (pinfunction "B_2") (pintype "passive"))
      (node (ref "R19") (pin "1") (pinfunction "1_1") (pintype "passive"))
    )
    (net (code "35") (name "Net-(Q7-C)") (class "Default")
      (node (ref "C4") (pin "1") (pinfunction "1_1") (pintype "passive"))
      (node (ref "C5") (pin "1") (pinfunction "1_1") (pintype "passive"))
      (node (ref "D41") (pin "C") (pinfunction "C_C") (pintype "passive"))
      (node (ref "Q7") (pin "3") (pinfunction "C_3") (pintype "passive"))
      (node (ref "R21") (pin "2") (pinfunction "2_2") (pintype "passive"))
    )
    (net (code "36") (name "Net-(Q8-B)") (class "Default")
      (node (ref "D40") (pin "A") (pinfunction "A_A") (pintype "passive"))
      (node (ref "Q8") (pin "2") (pinfunction "B_2") (pintype "passive"))
      (node (ref "R22") (pin "1") (pinfunction "1_1") (pintype "passive"))
    )
    (net (code "37") (name "Net-(Q8-C)") (class "Default")
      (node (ref "D42") (pin "C") (pinfunction "C_C") (pintype "passive"))
      (node (ref "D45") (pin "A") (pinfunction "A_A") (pintype "passive"))
      (node (ref "Q8") (pin "3") (pinfunction "C_3") (pintype "passive"))
      (node (ref "R24") (pin "2") (pinfunction "2_2") (pintype "passive"))
    )
    (net (code "38") (name "Net-(Q9-B)") (class "Default")
      (node (ref "Q9") (pin "2") (pinfunction "B_2") (pintype "passive"))
      (node (ref "R23") (pin "2") (pinfunction "2_2") (pintype "passive"))
      (node (ref "R25") (pin "1") (pinfunction "1_1") (pintype "passive"))
    )
    (net (code "39") (name "Net-(Q9-C)") (class "Default")
      (node (ref "C6") (pin "1") (pinfunction "1_1") (pintype "passive"))
      (node (ref "D44") (pin "A") (pinfunction "A_A") (pintype "passive"))
      (node (ref "D46") (pin "A") (pinfunction "A_A") (pintype "passive"))
      (node (ref "D49") (pin "C") (pinfunction "C_C") (pintype "passive"))
      (node (ref "Q9") (pin "3") (pinfunction "C_3") (pintype "passive"))
      (node (ref "R27") (pin "2") (pinfunction "2_2") (pintype "passive"))
      (node (ref "R29") (pin "1") (pinfunction "1_1") (pintype "passive"))
      (node (ref "U$2") (pin "AE2") (pinfunction "1_AE2") (pintype "bidirectional"))
    )
    (net (code "40") (name "Net-(Q10-B)") (class "Default")
      (node (ref "D48") (pin "A") (pinfunction "A_A") (pintype "passive"))
      (node (ref "Q10") (pin "2") (pinfunction "B_2") (pintype "passive"))
      (node (ref "R28") (pin "1") (pinfunction "1_1") (pintype "passive"))
    )
    (net (code "41") (name "Net-(Q10-C)") (class "Default")
      (node (ref "C7") (pin "1") (pinfunction "1_1") (pintype "passive"))
      (node (ref "C8") (pin "1") (pinfunction "1_1") (pintype "passive"))
      (node (ref "D51") (pin "C") (pinfunction "C_C") (pintype "passive"))
      (node (ref "Q10") (pin "3") (pinfunction "C_3") (pintype "passive"))
      (node (ref "R30") (pin "2") (pinfunction "2_2") (pintype "passive"))
    )
    (net (code "42") (name "Net-(Q11-B)") (class "Default")
      (node (ref "C6") (pin "2") (pinfunction "2_2") (pintype "passive"))
      (node (ref "Q11") (pin "2") (pinfunction "B_2") (pintype "passive"))
      (node (ref "R29") (pin "2") (pinfunction "2_2") (pintype "passive"))
    )
    (net (code "43") (name "Net-(Q11-C)") (class "Default")
      (node (ref "D50") (pin "C") (pinfunction "C_C") (pintype "passive"))
      (node (ref "Q11") (pin "3") (pinfunction "C_3") (pintype "passive"))
      (node (ref "R31") (pin "2") (pinfunction "2_2") (pintype "passive"))
      (node (ref "U$2") (pin "AF2") (pinfunction "1_AF2") (pintype "bidirectional"))
    )
    (net (code "44") (name "Net-(Q12-B)") (class "Default")
      (node (ref "Q12") (pin "2") (pinfunction "B_2") (pintype "passive"))
      (node (ref "R32") (pin "2") (pinfunction "2_2") (pintype "passive"))
      (node (ref "R33") (pin "1") (pinfunction "1_1") (pintype "passive"))
    )
    (net (code "45") (name "Net-(Q12-C)") (class "Default")
      (node (ref "C9") (pin "1") (pinfunction "1_1") (pintype "passive"))
      (node (ref "D53") (pin "A") (pinfunction "A_A") (pintype "passive"))
      (node (ref "D54") (pin "A") (pinfunction "A_A") (pintype "passive"))
      (node (ref "D55") (pin "C") (pinfunction "C_C") (pintype "passive"))
      (node (ref "Q12") (pin "3") (pinfunction "C_3") (pintype "passive"))
      (node (ref "R34") (pin "2") (pinfunction "2_2") (pintype "passive"))
      (node (ref "R36") (pin "1") (pinfunction "1_1") (pintype "passive"))
      (node (ref "U$2") (pin "AL2") (pinfunction "1_AL2") (pintype "bidirectional"))
    )
    (net (code "46") (name "Net-(Q13-B)") (class "Default")
      (node (ref "C9") (pin "2") (pinfunction "2_2") (pintype "passive"))
      (node (ref "Q13") (pin "2") (pinfunction "B_2") (pintype "passive"))
      (node (ref "R36") (pin "2") (pinfunction "2_2") (pintype "passive"))
    )
    (net (code "47") (name "Net-(Q13-C)") (class "Default")
      (node (ref "D60") (pin "C") (pinfunction "C_C") (pintype "passive"))
      (node (ref "Q13") (pin "3") (pinfunction "C_3") (pintype "passive"))
      (node (ref "R37") (pin "2") (pinfunction "2_2") (pintype "passive"))
      (node (ref "U$2") (pin "AM2") (pinfunction "1_AM2") (pintype "bidirectional"))
    )
    (net (code "48") (name "Net-(U$2AB-1)") (class "Default")
      (node (ref "D1") (pin "A") (pinfunction "A_A") (pintype "passive"))
      (node (ref "U$2") (pin "AR2") (pinfunction "1_AR2") (pintype "bidirectional"))
    )
    (net (code "49") (name "Net-(U$2AH-1)") (class "Default")
      (node (ref "C1") (pin "2") (pinfunction "2_2") (pintype "passive"))
      (node (ref "U$2") (pin "AU2") (pinfunction "1_AU2") (pintype "bidirectional"))
    )
    (net (code "50") (name "Net-(U$2AJ-1)") (class "Default")
      (node (ref "C2") (pin "2") (pinfunction "2_2") (pintype "passive"))
      (node (ref "D26") (pin "A") (pinfunction "A_A") (pintype "passive"))
      (node (ref "D27") (pin "C") (pinfunction "C_C") (pintype "passive"))
      (node (ref "R10") (pin "1") (pinfunction "1_1") (pintype "passive"))
      (node (ref "U$2") (pin "AV2") (pinfunction "1_AV2") (pintype "bidirectional"))
    )
    (net (code "51") (name "Net-(U$2AT-1)") (class "Default")
      (node (ref "D18") (pin "A") (pinfunction "A_A") (pintype "passive"))
      (node (ref "U$2") (pin "BE2") (pinfunction "1_BE2") (pintype "bidirectional"))
    )
    (net (code "52") (name "Net-(U$2AV-1)") (class "Default")
      (node (ref "D17") (pin "A") (pinfunction "A_A") (pintype "passive"))
      (node (ref "U$2") (pin "BF2") (pinfunction "1_BF2") (pintype "bidirectional"))
    )
    (net (code "53") (name "Net-(U$2AX-1)") (class "Default")
      (node (ref "D16") (pin "A") (pinfunction "A_A") (pintype "passive"))
      (node (ref "U$2") (pin "BH2") (pinfunction "1_BH2") (pintype "bidirectional"))
    )
    (net (code "54") (name "Net-(U$2AZ-1)") (class "Default")
      (node (ref "D15") (pin "A") (pinfunction "A_A") (pintype "passive"))
      (node (ref "U$2") (pin "BJ2") (pinfunction "1_BJ2") (pintype "bidirectional"))
    )
    (net (code "55") (name "Net-(U$2BB-1)") (class "Default")
      (node (ref "D14") (pin "A") (pinfunction "A_A") (pintype "passive"))
      (node (ref "U$2") (pin "BK2") (pinfunction "1_BK2") (pintype "bidirectional"))
    )
    (net (code "56") (name "Net-(U$2BD-1)") (class "Default")
      (node (ref "D13") (pin "A") (pinfunction "A_A") (pintype "passive"))
      (node (ref "U$2") (pin "BL2") (pinfunction "1_BL2") (pintype "bidirectional"))
    )
    (net (code "57") (name "Net-(U$2BF-1)") (class "Default")
      (node (ref "D12") (pin "A") (pinfunction "A_A") (pintype "passive"))
      (node (ref "U$2") (pin "BM2") (pinfunction "1_BM2") (pintype "bidirectional"))
    )
    (net (code "58") (name "Net-(U$2BH-1)") (class "Default")
      (node (ref "D11") (pin "A") (pinfunction "A_A") (pintype "passive"))
      (node (ref "U$2") (pin "BN2") (pinfunction "1_BN2") (pintype "bidirectional"))
    )
    (net (code "59") (name "Net-(U$2BJ-1)") (class "Default")
      (node (ref "D10") (pin "A") (pinfunction "A_A") (pintype "passive"))
      (node (ref "U$2") (pin "BP2") (pinfunction "1_BP2") (pintype "bidirectional"))
    )
    (net (code "60") (name "Net-(U$2BL-1)") (class "Default")
      (node (ref "D9") (pin "A") (pinfunction "A_A") (pintype "passive"))
      (node (ref "U$2") (pin "BR2") (pinfunction "1_BR2") (pintype "bidirectional"))
    )
    (net (code "61") (name "Net-(U$2BN-1)") (class "Default")
      (node (ref "D8") (pin "A") (pinfunction "A_A") (pintype "passive"))
      (node (ref "U$2") (pin "BS2") (pinfunction "1_BS2") (pintype "bidirectional"))
    )
    (net (code "62") (name "Net-(U$2BP-1)") (class "Default")
      (node (ref "D7") (pin "A") (pinfunction "A_A") (pintype "passive"))
      (node (ref "U$2") (pin "BT2") (pinfunction "1_BT2") (pintype "bidirectional"))
    )
    (net (code "63") (name "Net-(U$2BR-1)") (class "Default")
      (node (ref "D6") (pin "A") (pinfunction "A_A") (pintype "passive"))
      (node (ref "U$2") (pin "BU2") (pinfunction "1_BU2") (pintype "bidirectional"))
    )
    (net (code "64") (name "Net-(U$2BT-1)") (class "Default")
      (node (ref "D5") (pin "A") (pinfunction "A_A") (pintype "passive"))
      (node (ref "U$2") (pin "BV2") (pinfunction "1_BV2") (pintype "bidirectional"))
    )
    (net (code "65") (name "Net-(U$2H-1)") (class "Default")
      (node (ref "D29") (pin "A") (pinfunction "A_A") (pintype "passive"))
      (node (ref "U$2") (pin "AD2") (pinfunction "1_AD2") (pintype "bidirectional"))
    )
    (net (code "66") (name "Net-(U$2N-1)") (class "Default")
      (node (ref "C4") (pin "2") (pinfunction "2_2") (pintype "passive"))
      (node (ref "U$2") (pin "AH2") (pinfunction "1_AH2") (pintype "bidirectional"))
    )
    (net (code "67") (name "Net-(U$2P-1)") (class "Default")
      (node (ref "C5") (pin "2") (pinfunction "2_2") (pintype "passive"))
      (node (ref "D43") (pin "A") (pinfunction "A_A") (pintype "passive"))
      (node (ref "D44") (pin "C") (pinfunction "C_C") (pintype "passive"))
      (node (ref "R23") (pin "1") (pinfunction "1_1") (pintype "passive"))
      (node (ref "U$2") (pin "AJ2") (pinfunction "1_AJ2") (pintype "bidirectional"))
    )
    (net (code "68") (name "Net-(U$2R-1)") (class "Default")
      (node (ref "D38") (pin "A") (pinfunction "A_A") (pintype "passive"))
      (node (ref "U$2") (pin "AK2") (pinfunction "1_AK2") (pintype "bidirectional"))
    )
    (net (code "69") (name "Net-(U$2X-1)") (class "Default")
      (node (ref "C7") (pin "2") (pinfunction "2_2") (pintype "passive"))
      (node (ref "U$2") (pin "AN2") (pinfunction "1_AN2") (pintype "bidirectional"))
    )
    (net (code "70") (name "Net-(U$2Z-1)") (class "Default")
      (node (ref "C8") (pin "2") (pinfunction "2_2") (pintype "passive"))
      (node (ref "D52") (pin "A") (pinfunction "A_A") (pintype "passive"))
      (node (ref "D53") (pin "C") (pinfunction "C_C") (pintype "passive"))
      (node (ref "R32") (pin "1") (pinfunction "1_1") (pintype "passive"))
      (node (ref "U$2") (pin "AP2") (pinfunction "1_AP2") (pintype "bidirectional"))
    )
  )
)
